# LC_BigOne_-_165_SerialIn_Register.net
KiCad netlist of a schematic drawn in Altium Designer
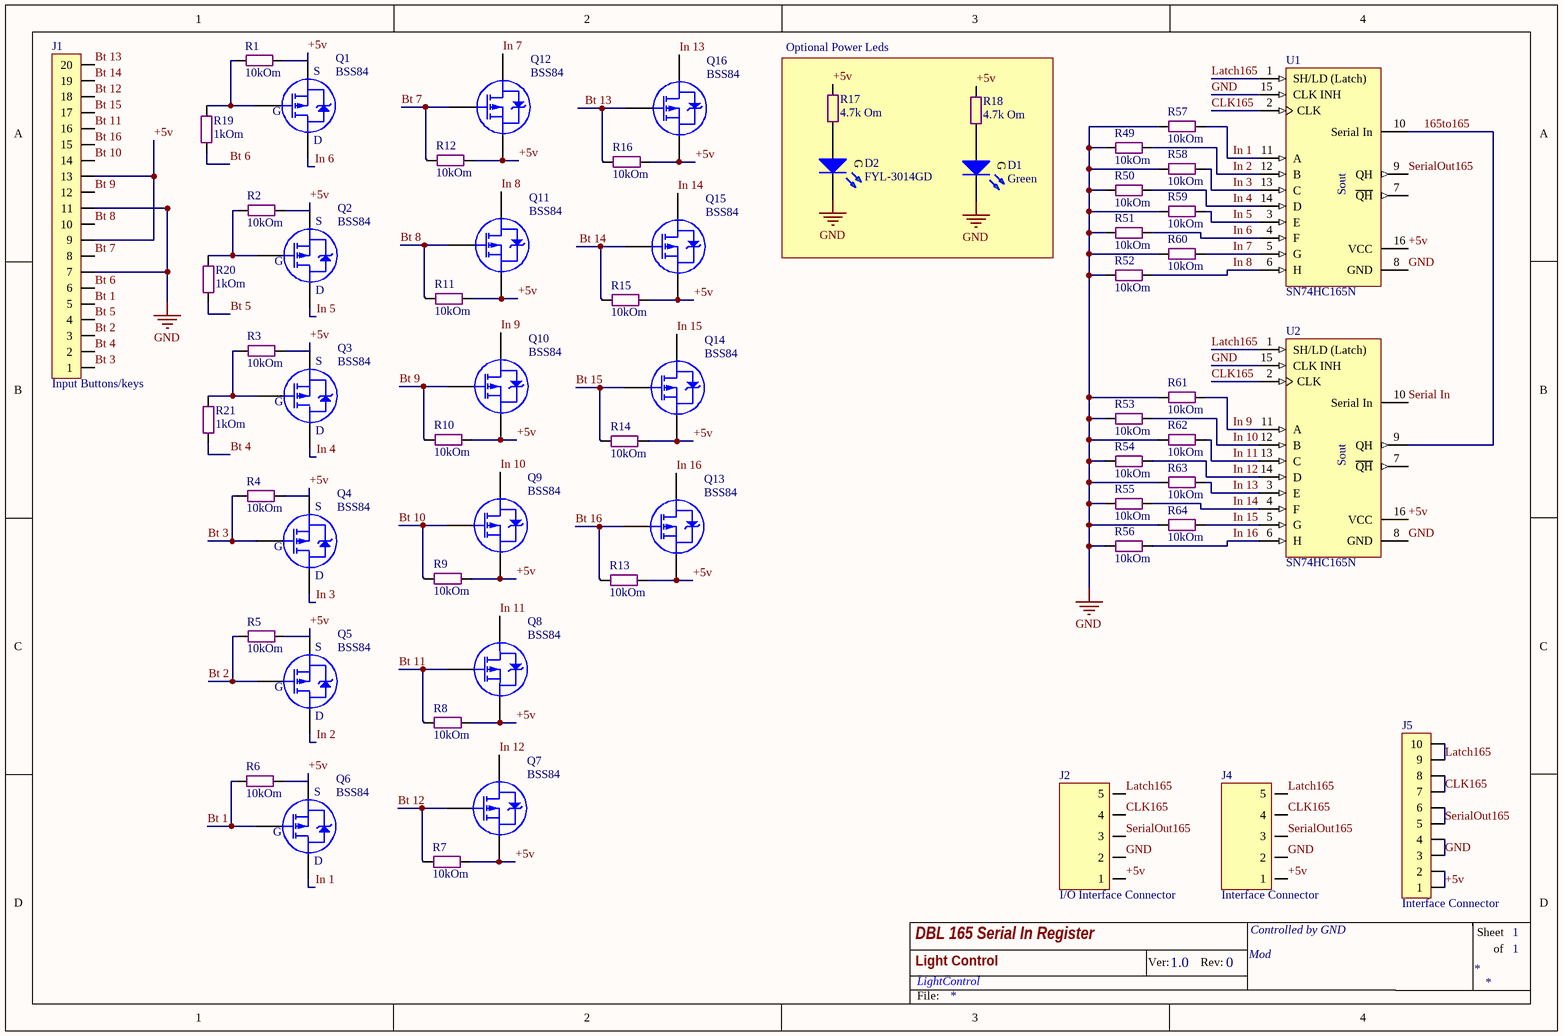
[diagram p0: LC BigOne - 165 SerialIn Register.SchDoc]

(export (version "E")
  (design (tool "Eeschema 10.0.6"))
  (components
    (comp (ref "D1")
      (value "Green")
      (footprint "LED:LED SMD 0805 Green")
      (description "?2v ?20mA")
      (libsource (lib "LED") (part "Led SMD Green"))
    )
    (comp (ref "D2")
      (value "FYL-3014GD")
      (footprint "LED:LED Round 3mm Green")
      (description "2.1v 10mA, 15-30mCd")
      (libsource (lib "LED") (part "Led Round 3mm Green"))
    )
    (comp (ref "J1")
      (value "Input Buttons/keys")
      (footprint "Connector:LINE 2.54 x 20D (2 x 10) - BH")
      (description "Vert, Dbl line, Male")
      (libsource (lib "Connector") (part "PLD-20 (2 x 10)"))
    )
    (comp (ref "J2")
      (value "I/O Interface Connector")
      (footprint "Connector:Line 2.54 x 5")
      (description "Vert, Sgl line, Male")
      (libsource (lib "Connector") (part "PLS-5"))
    )
    (comp (ref "J4")
      (value "Interface Connector")
      (footprint "Connector:Line 2.54 x 5")
      (description "Vert, Sgl line, Male")
      (libsource (lib "Connector") (part "PLS-5"))
    )
    (comp (ref "J5")
      (value "Interface Connector")
      (footprint "Connector:LINE 2.54 x 10D (2 x 5) - BH")
      (description "Vert, Dbl line, Male")
      (libsource (lib "Connector") (part "PLD-10 (2 x 5)"))
    )
    (comp (ref "Q1")
      (value "BSS84")
      (footprint "GeneralCases:SOT-23")
      (description "P-Channel -50V - 10-1Ω - 0.13A")
      (libsource (lib "Transistor") (part "BSS84"))
    )
    (comp (ref "Q2")
      (value "BSS84")
      (footprint "GeneralCases:SOT-23")
      (description "P-Channel -50V - 10-1Ω - 0.13A")
      (libsource (lib "Transistor") (part "BSS84"))
    )
    (comp (ref "Q3")
      (value "BSS84")
      (footprint "GeneralCases:SOT-23")
      (description "P-Channel -50V - 10-1Ω - 0.13A")
      (libsource (lib "Transistor") (part "BSS84"))
    )
    (comp (ref "Q4")
      (value "BSS84")
      (footprint "GeneralCases:SOT-23")
      (description "P-Channel -50V - 10-1Ω - 0.13A")
      (libsource (lib "Transistor") (part "BSS84"))
    )
    (comp (ref "Q5")
      (value "BSS84")
      (footprint "GeneralCases:SOT-23")
      (description "P-Channel -50V - 10-1Ω - 0.13A")
      (libsource (lib "Transistor") (part "BSS84"))
    )
    (comp (ref "Q6")
      (value "BSS84")
      (footprint "GeneralCases:SOT-23")
      (description "P-Channel -50V - 10-1Ω - 0.13A")
      (libsource (lib "Transistor") (part "BSS84"))
    )
    (comp (ref "Q7")
      (value "BSS84")
      (footprint "GeneralCases:SOT-23")
      (description "P-Channel -50V - 10-1Ω - 0.13A")
      (libsource (lib "") (part "BSS84_1"))
    )
    (comp (ref "Q8")
      (value "BSS84")
      (footprint "GeneralCases:SOT-23")
      (description "P-Channel -50V - 10-1Ω - 0.13A")
      (libsource (lib "") (part "BSS84_1"))
    )
    (comp (ref "Q9")
      (value "BSS84")
      (footprint "GeneralCases:SOT-23")
      (description "P-Channel -50V - 10-1Ω - 0.13A")
      (libsource (lib "") (part "BSS84_1"))
    )
    (comp (ref "Q10")
      (value "BSS84")
      (footprint "GeneralCases:SOT-23")
      (description "P-Channel -50V - 10-1Ω - 0.13A")
      (libsource (lib "") (part "BSS84_1"))
    )
    (comp (ref "Q11")
      (value "BSS84")
      (footprint "GeneralCases:SOT-23")
      (description "P-Channel -50V - 10-1Ω - 0.13A")
      (libsource (lib "") (part "BSS84_1"))
    )
    (comp (ref "Q12")
      (value "BSS84")
      (footprint "GeneralCases:SOT-23")
      (description "P-Channel -50V - 10-1Ω - 0.13A")
      (libsource (lib "") (part "BSS84_1"))
    )
    (comp (ref "Q13")
      (value "BSS84")
      (footprint "GeneralCases:SOT-23")
      (description "P-Channel -50V - 10-1Ω - 0.13A")
      (libsource (lib "") (part "BSS84_1"))
    )
    (comp (ref "Q14")
      (value "BSS84")
      (footprint "GeneralCases:SOT-23")
      (description "P-Channel -50V - 10-1Ω - 0.13A")
      (libsource (lib "") (part "BSS84_1"))
    )
    (comp (ref "Q15")
      (value "BSS84")
      (footprint "GeneralCases:SOT-23")
      (description "P-Channel -50V - 10-1Ω - 0.13A")
      (libsource (lib "") (part "BSS84_1"))
    )
    (comp (ref "Q16")
      (value "BSS84")
      (footprint "GeneralCases:SOT-23")
      (description "P-Channel -50V - 10-1Ω - 0.13A")
      (libsource (lib "") (part "BSS84_1"))
    )
    (comp (ref "R1")
      (value "10kOm")
      (footprint "PassiveComponents:SMD 0603 (1608)")
      (libsource (lib "PassiveComponents") (part "Res All Types"))
    )
    (comp (ref "R2")
      (value "10kOm")
      (footprint "PassiveComponents:SMD 0603 (1608)")
      (libsource (lib "PassiveComponents") (part "Res All Types"))
    )
    (comp (ref "R3")
      (value "10kOm")
      (footprint "PassiveComponents:SMD 0603 (1608)")
      (libsource (lib "PassiveComponents") (part "Res All Types"))
    )
    (comp (ref "R4")
      (value "10kOm")
      (footprint "PassiveComponents:SMD 0805 (2012)")
      (libsource (lib "PassiveComponents") (part "Res All Types"))
    )
    (comp (ref "R5")
      (value "10kOm")
      (footprint "PassiveComponents:SMD 0805 (2012)")
      (libsource (lib "PassiveComponents") (part "Res All Types"))
    )
    (comp (ref "R6")
      (value "10kOm")
      (footprint "PassiveComponents:SMD 0805 (2012)")
      (libsource (lib "PassiveComponents") (part "Res All Types"))
    )
    (comp (ref "R7")
      (value "10kOm")
      (footprint "PassiveComponents:SMD 0805 (2012)")
      (libsource (lib "PassiveComponents") (part "Res All Types"))
    )
    (comp (ref "R8")
      (value "10kOm")
      (footprint "PassiveComponents:SMD 0805 (2012)")
      (libsource (lib "PassiveComponents") (part "Res All Types"))
    )
    (comp (ref "R9")
      (value "10kOm")
      (footprint "PassiveComponents:SMD 0805 (2012)")
      (libsource (lib "PassiveComponents") (part "Res All Types"))
    )
    (comp (ref "R10")
      (value "10kOm")
      (footprint "PassiveComponents:SMD 0805 (2012)")
      (libsource (lib "PassiveComponents") (part "Res All Types"))
    )
    (comp (ref "R11")
      (value "10kOm")
      (footprint "PassiveComponents:SMD 0805 (2012)")
      (libsource (lib "PassiveComponents") (part "Res All Types"))
    )
    (comp (ref "R12")
      (value "10kOm")
      (footprint "PassiveComponents:SMD 0805 (2012)")
      (libsource (lib "PassiveComponents") (part "Res All Types"))
    )
    (comp (ref "R13")
      (value "10kOm")
      (footprint "PassiveComponents:SMD 0805 (2012)")
      (libsource (lib "PassiveComponents") (part "Res All Types"))
    )
    (comp (ref "R14")
      (value "10kOm")
      (footprint "PassiveComponents:SMD 0805 (2012)")
      (libsource (lib "PassiveComponents") (part "Res All Types"))
    )
    (comp (ref "R15")
      (value "10kOm")
      (footprint "PassiveComponents:SMD 0805 (2012)")
      (libsource (lib "PassiveComponents") (part "Res All Types"))
    )
    (comp (ref "R16")
      (value "10kOm")
      (footprint "PassiveComponents:SMD 0805 (2012)")
      (libsource (lib "PassiveComponents") (part "Res All Types"))
    )
    (comp (ref "R17")
      (value "4.7k Om")
      (footprint "PassiveComponents:SMD 0805 (2012)")
      (libsource (lib "PassiveComponents") (part "Res All Types"))
    )
    (comp (ref "R18")
      (value "4.7k Om")
      (footprint "PassiveComponents:SMD 0805 (2012)")
      (libsource (lib "PassiveComponents") (part "Res All Types"))
    )
    (comp (ref "R19")
      (value "1kOm")
      (footprint "PassiveComponents:SMD 0603 (1608)")
      (libsource (lib "PassiveComponents") (part "Res All Types"))
    )
    (comp (ref "R20")
      (value "1kOm")
      (footprint "PassiveComponents:SMD 0603 (1608)")
      (libsource (lib "PassiveComponents") (part "Res All Types"))
    )
    (comp (ref "R21")
      (value "1kOm")
      (footprint "PassiveComponents:SMD 0603 (1608)")
      (libsource (lib "PassiveComponents") (part "Res All Types"))
    )
    (comp (ref "R49")
      (value "10kOm")
      (footprint "PassiveComponents:SMD 0805 (2012)")
      (libsource (lib "PassiveComponents") (part "Res All Types"))
    )
    (comp (ref "R50")
      (value "10kOm")
      (footprint "PassiveComponents:SMD 0805 (2012)")
      (libsource (lib "PassiveComponents") (part "Res All Types"))
    )
    (comp (ref "R51")
      (value "10kOm")
      (footprint "PassiveComponents:SMD 0805 (2012)")
      (libsource (lib "PassiveComponents") (part "Res All Types"))
    )
    (comp (ref "R52")
      (value "10kOm")
      (footprint "PassiveComponents:SMD 0805 (2012)")
      (libsource (lib "PassiveComponents") (part "Res All Types"))
    )
    (comp (ref "R53")
      (value "10kOm")
      (footprint "PassiveComponents:SMD 0805 (2012)")
      (libsource (lib "PassiveComponents") (part "Res All Types"))
    )
    (comp (ref "R54")
      (value "10kOm")
      (footprint "PassiveComponents:SMD 0805 (2012)")
      (libsource (lib "PassiveComponents") (part "Res All Types"))
    )
    (comp (ref "R55")
      (value "10kOm")
      (footprint "PassiveComponents:SMD 0805 (2012)")
      (libsource (lib "PassiveComponents") (part "Res All Types"))
    )
    (comp (ref "R56")
      (value "10kOm")
      (footprint "PassiveComponents:SMD 0805 (2012)")
      (libsource (lib "PassiveComponents") (part "Res All Types"))
    )
    (comp (ref "R57")
      (value "10kOm")
      (footprint "PassiveComponents:SMD 0805 (2012)")
      (libsource (lib "PassiveComponents") (part "Res All Types"))
    )
    (comp (ref "R58")
      (value "10kOm")
      (footprint "PassiveComponents:SMD 0805 (2012)")
      (libsource (lib "PassiveComponents") (part "Res All Types"))
    )
    (comp (ref "R59")
      (value "10kOm")
      (footprint "PassiveComponents:SMD 0805 (2012)")
      (libsource (lib "PassiveComponents") (part "Res All Types"))
    )
    (comp (ref "R60")
      (value "10kOm")
      (footprint "PassiveComponents:SMD 0805 (2012)")
      (libsource (lib "PassiveComponents") (part "Res All Types"))
    )
    (comp (ref "R61")
      (value "10kOm")
      (footprint "PassiveComponents:SMD 0805 (2012)")
      (libsource (lib "PassiveComponents") (part "Res All Types"))
    )
    (comp (ref "R62")
      (value "10kOm")
      (footprint "PassiveComponents:SMD 0805 (2012)")
      (libsource (lib "PassiveComponents") (part "Res All Types"))
    )
    (comp (ref "R63")
      (value "10kOm")
      (footprint "PassiveComponents:SMD 0805 (2012)")
      (libsource (lib "PassiveComponents") (part "Res All Types"))
    )
    (comp (ref "R64")
      (value "10kOm")
      (footprint "PassiveComponents:SMD 0805 (2012)")
      (libsource (lib "PassiveComponents") (part "Res All Types"))
    )
    (comp (ref "U1")
      (value "SN74HC165N")
      (footprint "GeneralCases:DIP-16")
      (description "8-Bit Parallel-Load Shift Register")
      (fields (field (name "PUBLISHER") "Altium Limited"))
      (libsource (lib "Chips") (part "SN74HC165N"))
    )
    (comp (ref "U2")
      (value "SN74HC165N")
      (footprint "GeneralCases:DIP-16")
      (description "8-Bit Parallel-Load Shift Register")
      (fields (field (name "PUBLISHER") "Altium Limited"))
      (libsource (lib "Chips") (part "SN74HC165N"))
    )
  )
  (nets
    (net (code "1") (name "/+5v") (class "Default")
      (node (ref "J1") (pin "13") (pinfunction "13_13") (pintype "passive"))
      (node (ref "J1") (pin "9") (pinfunction "9_9") (pintype "passive"))
      (node (ref "J2") (pin "1") (pinfunction "1_1") (pintype "passive"))
      (node (ref "J4") (pin "1") (pinfunction "1_1") (pintype "passive"))
      (node (ref "J5") (pin "1") (pinfunction "1_1") (pintype "passive"))
      (node (ref "J5") (pin "2") (pinfunction "2_2") (pintype "passive"))
      (node (ref "Q1") (pin "2") (pinfunction "S_2") (pintype "passive"))
      (node (ref "Q10") (pin "3") (pinfunction "S_3") (pintype "passive"))
      (node (ref "Q11") (pin "3") (pinfunction "S_3") (pintype "passive"))
      (node (ref "Q12") (pin "3") (pinfunction "S_3") (pintype "passive"))
      (node (ref "Q13") (pin "3") (pinfunction "S_3") (pintype "passive"))
      (node (ref "Q14") (pin "3") (pinfunction "S_3") (pintype "passive"))
      (node (ref "Q15") (pin "3") (pinfunction "S_3") (pintype "passive"))
      (node (ref "Q16") (pin "3") (pinfunction "S_3") (pintype "passive"))
      (node (ref "Q2") (pin "2") (pinfunction "S_2") (pintype "passive"))
      (node (ref "Q3") (pin "2") (pinfunction "S_2") (pintype "passive"))
      (node (ref "Q4") (pin "2") (pinfunction "S_2") (pintype "passive"))
      (node (ref "Q5") (pin "2") (pinfunction "S_2") (pintype "passive"))
      (node (ref "Q6") (pin "2") (pinfunction "S_2") (pintype "passive"))
      (node (ref "Q7") (pin "3") (pinfunction "S_3") (pintype "passive"))
      (node (ref "Q8") (pin "3") (pinfunction "S_3") (pintype "passive"))
      (node (ref "Q9") (pin "3") (pinfunction "S_3") (pintype "passive"))
      (node (ref "R1") (pin "1") (pinfunction "1_1") (pintype "passive"))
      (node (ref "R10") (pin "1") (pinfunction "1_1") (pintype "passive"))
      (node (ref "R11") (pin "1") (pinfunction "1_1") (pintype "passive"))
      (node (ref "R12") (pin "1") (pinfunction "1_1") (pintype "passive"))
      (node (ref "R13") (pin "1") (pinfunction "1_1") (pintype "passive"))
      (node (ref "R14") (pin "1") (pinfunction "1_1") (pintype "passive"))
      (node (ref "R15") (pin "1") (pinfunction "1_1") (pintype "passive"))
      (node (ref "R16") (pin "1") (pinfunction "1_1") (pintype "passive"))
      (node (ref "R17") (pin "1") (pinfunction "1_1") (pintype "passive"))
      (node (ref "R18") (pin "1") (pinfunction "1_1") (pintype "passive"))
      (node (ref "R2") (pin "1") (pinfunction "1_1") (pintype "passive"))
      (node (ref "R3") (pin "1") (pinfunction "1_1") (pintype "passive"))
      (node (ref "R4") (pin "1") (pinfunction "1_1") (pintype "passive"))
      (node (ref "R5") (pin "1") (pinfunction "1_1") (pintype "passive"))
      (node (ref "R6") (pin "1") (pinfunction "1_1") (pintype "passive"))
      (node (ref "R7") (pin "1") (pinfunction "1_1") (pintype "passive"))
      (node (ref "R8") (pin "1") (pinfunction "1_1") (pintype "passive"))
      (node (ref "R9") (pin "1") (pinfunction "1_1") (pintype "passive"))
      (node (ref "U1") (pin "16") (pinfunction "VCC_16") (pintype "power_in"))
      (node (ref "U2") (pin "16") (pinfunction "VCC_16") (pintype "power_in"))
    )
    (net (code "2") (name "/165to165") (class "Default")
      (node (ref "U1") (pin "10") (pinfunction "Serial_In_10") (pintype "passive"))
      (node (ref "U2") (pin "9") (pinfunction "QH_9") (pintype "output"))
    )
    (net (code "3") (name "/Bt 1") (class "Default")
      (node (ref "J1") (pin "5") (pinfunction "5_5") (pintype "passive"))
      (node (ref "Q6") (pin "1") (pinfunction "G_1") (pintype "passive"))
      (node (ref "R6") (pin "2") (pinfunction "2_2") (pintype "passive"))
    )
    (net (code "4") (name "/Bt 2") (class "Default")
      (node (ref "J1") (pin "3") (pinfunction "3_3") (pintype "passive"))
      (node (ref "Q5") (pin "1") (pinfunction "G_1") (pintype "passive"))
      (node (ref "R5") (pin "2") (pinfunction "2_2") (pintype "passive"))
    )
    (net (code "5") (name "/Bt 3") (class "Default")
      (node (ref "J1") (pin "1") (pinfunction "1_1") (pintype "passive"))
      (node (ref "Q4") (pin "1") (pinfunction "G_1") (pintype "passive"))
      (node (ref "R4") (pin "2") (pinfunction "2_2") (pintype "passive"))
    )
    (net (code "6") (name "/Bt 4") (class "Default")
      (node (ref "J1") (pin "2") (pinfunction "2_2") (pintype "passive"))
      (node (ref "R21") (pin "2") (pinfunction "2_2") (pintype "passive"))
    )
    (net (code "7") (name "/Bt 5") (class "Default")
      (node (ref "J1") (pin "4") (pinfunction "4_4") (pintype "passive"))
      (node (ref "R20") (pin "2") (pinfunction "2_2") (pintype "passive"))
    )
    (net (code "8") (name "/Bt 6") (class "Default")
      (node (ref "J1") (pin "6") (pinfunction "6_6") (pintype "passive"))
      (node (ref "R19") (pin "2") (pinfunction "2_2") (pintype "passive"))
    )
    (net (code "9") (name "/Bt 7") (class "Default")
      (node (ref "J1") (pin "8") (pinfunction "8_8") (pintype "passive"))
      (node (ref "Q12") (pin "1") (pinfunction "G_1") (pintype "passive"))
      (node (ref "R12") (pin "2") (pinfunction "2_2") (pintype "passive"))
    )
    (net (code "10") (name "/Bt 8") (class "Default")
      (node (ref "J1") (pin "10") (pinfunction "10_10") (pintype "passive"))
      (node (ref "Q11") (pin "1") (pinfunction "G_1") (pintype "passive"))
      (node (ref "R11") (pin "2") (pinfunction "2_2") (pintype "passive"))
    )
    (net (code "11") (name "/Bt 9") (class "Default")
      (node (ref "J1") (pin "12") (pinfunction "12_12") (pintype "passive"))
      (node (ref "Q10") (pin "1") (pinfunction "G_1") (pintype "passive"))
      (node (ref "R10") (pin "2") (pinfunction "2_2") (pintype "passive"))
    )
    (net (code "12") (name "/Bt 10") (class "Default")
      (node (ref "J1") (pin "14") (pinfunction "14_14") (pintype "passive"))
      (node (ref "Q9") (pin "1") (pinfunction "G_1") (pintype "passive"))
      (node (ref "R9") (pin "2") (pinfunction "2_2") (pintype "passive"))
    )
    (net (code "13") (name "/Bt 11") (class "Default")
      (node (ref "J1") (pin "16") (pinfunction "16_16") (pintype "passive"))
      (node (ref "Q8") (pin "1") (pinfunction "G_1") (pintype "passive"))
      (node (ref "R8") (pin "2") (pinfunction "2_2") (pintype "passive"))
    )
    (net (code "14") (name "/Bt 12") (class "Default")
      (node (ref "J1") (pin "18") (pinfunction "18_18") (pintype "passive"))
      (node (ref "Q7") (pin "1") (pinfunction "G_1") (pintype "passive"))
      (node (ref "R7") (pin "2") (pinfunction "2_2") (pintype "passive"))
    )
    (net (code "15") (name "/Bt 13") (class "Default")
      (node (ref "J1") (pin "20") (pinfunction "20_20") (pintype "passive"))
      (node (ref "Q16") (pin "1") (pinfunction "G_1") (pintype "passive"))
      (node (ref "R16") (pin "2") (pinfunction "2_2") (pintype "passive"))
    )
    (net (code "16") (name "/Bt 14") (class "Default")
      (node (ref "J1") (pin "19") (pinfunction "19_19") (pintype "passive"))
      (node (ref "Q15") (pin "1") (pinfunction "G_1") (pintype "passive"))
      (node (ref "R15") (pin "2") (pinfunction "2_2") (pintype "passive"))
    )
    (net (code "17") (name "/Bt 15") (class "Default")
      (node (ref "J1") (pin "17") (pinfunction "17_17") (pintype "passive"))
      (node (ref "Q14") (pin "1") (pinfunction "G_1") (pintype "passive"))
      (node (ref "R14") (pin "2") (pinfunction "2_2") (pintype "passive"))
    )
    (net (code "18") (name "/Bt 16") (class "Default")
      (node (ref "J1") (pin "15") (pinfunction "15_15") (pintype "passive"))
      (node (ref "Q13") (pin "1") (pinfunction "G_1") (pintype "passive"))
      (node (ref "R13") (pin "2") (pinfunction "2_2") (pintype "passive"))
    )
    (net (code "19") (name "/CLK165") (class "Default")
      (node (ref "J2") (pin "4") (pinfunction "4_4") (pintype "passive"))
      (node (ref "J4") (pin "4") (pinfunction "4_4") (pintype "passive"))
      (node (ref "J5") (pin "7") (pinfunction "7_7") (pintype "passive"))
      (node (ref "J5") (pin "8") (pinfunction "8_8") (pintype "passive"))
      (node (ref "U1") (pin "2") (pinfunction "CLK_2") (pintype "input"))
      (node (ref "U2") (pin "2") (pinfunction "CLK_2") (pintype "input"))
    )
    (net (code "20") (name "/In 1") (class "Default")
      (node (ref "Q6") (pin "3") (pinfunction "D_3") (pintype "passive"))
      (node (ref "R57") (pin "2") (pinfunction "2_2") (pintype "passive"))
      (node (ref "U1") (pin "11") (pinfunction "A_11") (pintype "input"))
    )
    (net (code "21") (name "/In 2") (class "Default")
      (node (ref "Q5") (pin "3") (pinfunction "D_3") (pintype "passive"))
      (node (ref "R49") (pin "2") (pinfunction "2_2") (pintype "passive"))
      (node (ref "U1") (pin "12") (pinfunction "B_12") (pintype "input"))
    )
    (net (code "22") (name "/In 3") (class "Default")
      (node (ref "Q4") (pin "3") (pinfunction "D_3") (pintype "passive"))
      (node (ref "R58") (pin "2") (pinfunction "2_2") (pintype "passive"))
      (node (ref "U1") (pin "13") (pinfunction "C_13") (pintype "input"))
    )
    (net (code "23") (name "/In 4") (class "Default")
      (node (ref "Q3") (pin "3") (pinfunction "D_3") (pintype "passive"))
      (node (ref "R50") (pin "2") (pinfunction "2_2") (pintype "passive"))
      (node (ref "U1") (pin "14") (pinfunction "D_14") (pintype "input"))
    )
    (net (code "24") (name "/In 5") (class "Default")
      (node (ref "Q2") (pin "3") (pinfunction "D_3") (pintype "passive"))
      (node (ref "R59") (pin "2") (pinfunction "2_2") (pintype "passive"))
      (node (ref "U1") (pin "3") (pinfunction "E_3") (pintype "input"))
    )
    (net (code "25") (name "/In 6") (class "Default")
      (node (ref "Q1") (pin "3") (pinfunction "D_3") (pintype "passive"))
      (node (ref "R51") (pin "2") (pinfunction "2_2") (pintype "passive"))
      (node (ref "U1") (pin "4") (pinfunction "F_4") (pintype "input"))
    )
    (net (code "26") (name "/In 7") (class "Default")
      (node (ref "Q12") (pin "2") (pinfunction "D_2") (pintype "passive"))
      (node (ref "R60") (pin "2") (pinfunction "2_2") (pintype "passive"))
      (node (ref "U1") (pin "5") (pinfunction "G_5") (pintype "input"))
    )
    (net (code "27") (name "/In 8") (class "Default")
      (node (ref "Q11") (pin "2") (pinfunction "D_2") (pintype "passive"))
      (node (ref "R52") (pin "2") (pinfunction "2_2") (pintype "passive"))
      (node (ref "U1") (pin "6") (pinfunction "H_6") (pintype "input"))
    )
    (net (code "28") (name "/In 9") (class "Default")
      (node (ref "Q10") (pin "2") (pinfunction "D_2") (pintype "passive"))
      (node (ref "R61") (pin "2") (pinfunction "2_2") (pintype "passive"))
      (node (ref "U2") (pin "11") (pinfunction "A_11") (pintype "input"))
    )
    (net (code "29") (name "/In 10") (class "Default")
      (node (ref "Q9") (pin "2") (pinfunction "D_2") (pintype "passive"))
      (node (ref "R53") (pin "2") (pinfunction "2_2") (pintype "passive"))
      (node (ref "U2") (pin "12") (pinfunction "B_12") (pintype "input"))
    )
    (net (code "30") (name "/In 11") (class "Default")
      (node (ref "Q8") (pin "2") (pinfunction "D_2") (pintype "passive"))
      (node (ref "R62") (pin "2") (pinfunction "2_2") (pintype "passive"))
      (node (ref "U2") (pin "13") (pinfunction "C_13") (pintype "input"))
    )
    (net (code "31") (name "/In 12") (class "Default")
      (node (ref "Q7") (pin "2") (pinfunction "D_2") (pintype "passive"))
      (node (ref "R54") (pin "2") (pinfunction "2_2") (pintype "passive"))
      (node (ref "U2") (pin "14") (pinfunction "D_14") (pintype "input"))
    )
    (net (code "32") (name "/In 13") (class "Default")
      (node (ref "Q16") (pin "2") (pinfunction "D_2") (pintype "passive"))
      (node (ref "R63") (pin "2") (pinfunction "2_2") (pintype "passive"))
      (node (ref "U2") (pin "3") (pinfunction "E_3") (pintype "input"))
    )
    (net (code "33") (name "/In 14") (class "Default")
      (node (ref "Q15") (pin "2") (pinfunction "D_2") (pintype "passive"))
      (node (ref "R55") (pin "2") (pinfunction "2_2") (pintype "passive"))
      (node (ref "U2") (pin "4") (pinfunction "F_4") (pintype "input"))
    )
    (net (code "34") (name "/In 15") (class "Default")
      (node (ref "Q14") (pin "2") (pinfunction "D_2") (pintype "passive"))
      (node (ref "R64") (pin "2") (pinfunction "2_2") (pintype "passive"))
      (node (ref "U2") (pin "5") (pinfunction "G_5") (pintype "input"))
    )
    (net (code "35") (name "/In 16") (class "Default")
      (node (ref "Q13") (pin "2") (pinfunction "D_2") (pintype "passive"))
      (node (ref "R56") (pin "2") (pinfunction "2_2") (pintype "passive"))
      (node (ref "U2") (pin "6") (pinfunction "H_6") (pintype "input"))
    )
    (net (code "36") (name "/Latch165") (class "Default")
      (node (ref "J2") (pin "5") (pinfunction "5_5") (pintype "passive"))
      (node (ref "J4") (pin "5") (pinfunction "5_5") (pintype "passive"))
      (node (ref "J5") (pin "10") (pinfunction "10_10") (pintype "passive"))
      (node (ref "J5") (pin "9") (pinfunction "9_9") (pintype "passive"))
      (node (ref "U1") (pin "1") (pinfunction "SH/LD_(Latch)_1") (pintype "input"))
      (node (ref "U2") (pin "1") (pinfunction "SH/LD_(Latch)_1") (pintype "input"))
    )
    (net (code "37") (name "/Serial In") (class "Default")
      (node (ref "U2") (pin "10") (pinfunction "Serial_In_10") (pintype "passive"))
    )
    (net (code "38") (name "/SerialOut165") (class "Default")
      (node (ref "J2") (pin "3") (pinfunction "3_3") (pintype "passive"))
      (node (ref "J4") (pin "3") (pinfunction "3_3") (pintype "passive"))
      (node (ref "J5") (pin "5") (pinfunction "5_5") (pintype "passive"))
      (node (ref "J5") (pin "6") (pinfunction "6_6") (pintype "passive"))
      (node (ref "U1") (pin "9") (pinfunction "QH_9") (pintype "output"))
    )
    (net (code "39") (name "GND") (class "Default")
      (node (ref "D1") (pin "K") (pinfunction "K_K") (pintype "passive"))
      (node (ref "D2") (pin "K") (pinfunction "K_K") (pintype "passive"))
      (node (ref "J1") (pin "11") (pinfunction "11_11") (pintype "passive"))
      (node (ref "J1") (pin "7") (pinfunction "7_7") (pintype "passive"))
      (node (ref "J2") (pin "2") (pinfunction "2_2") (pintype "passive"))
      (node (ref "J4") (pin "2") (pinfunction "2_2") (pintype "passive"))
      (node (ref "J5") (pin "3") (pinfunction "3_3") (pintype "passive"))
      (node (ref "J5") (pin "4") (pinfunction "4_4") (pintype "passive"))
      (node (ref "R49") (pin "1") (pinfunction "1_1") (pintype "passive"))
      (node (ref "R50") (pin "1") (pinfunction "1_1") (pintype "passive"))
      (node (ref "R51") (pin "1") (pinfunction "1_1") (pintype "passive"))
      (node (ref "R52") (pin "1") (pinfunction "1_1") (pintype "passive"))
      (node (ref "R53") (pin "1") (pinfunction "1_1") (pintype "passive"))
      (node (ref "R54") (pin "1") (pinfunction "1_1") (pintype "passive"))
      (node (ref "R55") (pin "1") (pinfunction "1_1") (pintype "passive"))
      (node (ref "R56") (pin "1") (pinfunction "1_1") (pintype "passive"))
      (node (ref "R57") (pin "1") (pinfunction "1_1") (pintype "passive"))
      (node (ref "R58") (pin "1") (pinfunction "1_1") (pintype "passive"))
      (node (ref "R59") (pin "1") (pinfunction "1_1") (pintype "passive"))
      (node (ref "R60") (pin "1") (pinfunction "1_1") (pintype "passive"))
      (node (ref "R61") (pin "1") (pinfunction "1_1") (pintype "passive"))
      (node (ref "R62") (pin "1") (pinfunction "1_1") (pintype "passive"))
      (node (ref "R63") (pin "1") (pinfunction "1_1") (pintype "passive"))
      (node (ref "R64") (pin "1") (pinfunction "1_1") (pintype "passive"))
      (node (ref "U1") (pin "15") (pinfunction "CLK_INH_15") (pintype "input"))
      (node (ref "U1") (pin "8") (pinfunction "GND_8") (pintype "power_in"))
      (node (ref "U2") (pin "15") (pinfunction "CLK_INH_15") (pintype "input"))
      (node (ref "U2") (pin "8") (pinfunction "GND_8") (pintype "power_in"))
    )
    (net (code "40") (name "Net-(D1-PadA)") (class "Default")
      (node (ref "D1") (pin "A") (pinfunction "A_A") (pintype "passive"))
      (node (ref "R18") (pin "2") (pinfunction "2_2") (pintype "passive"))
    )
    (net (code "41") (name "Net-(D2-PadA)") (class "Default")
      (node (ref "D2") (pin "A") (pinfunction "A_A") (pintype "passive"))
      (node (ref "R17") (pin "2") (pinfunction "2_2") (pintype "passive"))
    )
    (net (code "42") (name "Net-(Q1-G)") (class "Default")
      (node (ref "Q1") (pin "1") (pinfunction "G_1") (pintype "passive"))
      (node (ref "R1") (pin "2") (pinfunction "2_2") (pintype "passive"))
      (node (ref "R19") (pin "1") (pinfunction "1_1") (pintype "passive"))
    )
    (net (code "43") (name "Net-(Q2-G)") (class "Default")
      (node (ref "Q2") (pin "1") (pinfunction "G_1") (pintype "passive"))
      (node (ref "R2") (pin "2") (pinfunction "2_2") (pintype "passive"))
      (node (ref "R20") (pin "1") (pinfunction "1_1") (pintype "passive"))
    )
    (net (code "44") (name "Net-(Q3-G)") (class "Default")
      (node (ref "Q3") (pin "1") (pinfunction "G_1") (pintype "passive"))
      (node (ref "R21") (pin "1") (pinfunction "1_1") (pintype "passive"))
      (node (ref "R3") (pin "2") (pinfunction "2_2") (pintype "passive"))
    )
    (net (code "45") (name "unconnected-(U1-~{QH}-Pad7)") (class "Default")
      (node (ref "U1") (pin "7") (pinfunction "~{QH}_7") (pintype "output"))
    )
    (net (code "46") (name "unconnected-(U2-~{QH}-Pad7)") (class "Default")
      (node (ref "U2") (pin "7") (pinfunction "~{QH}_7") (pintype "output"))
    )
  )
)
